# R650E.net
KiCad netlist of a schematic drawn in EAGLE
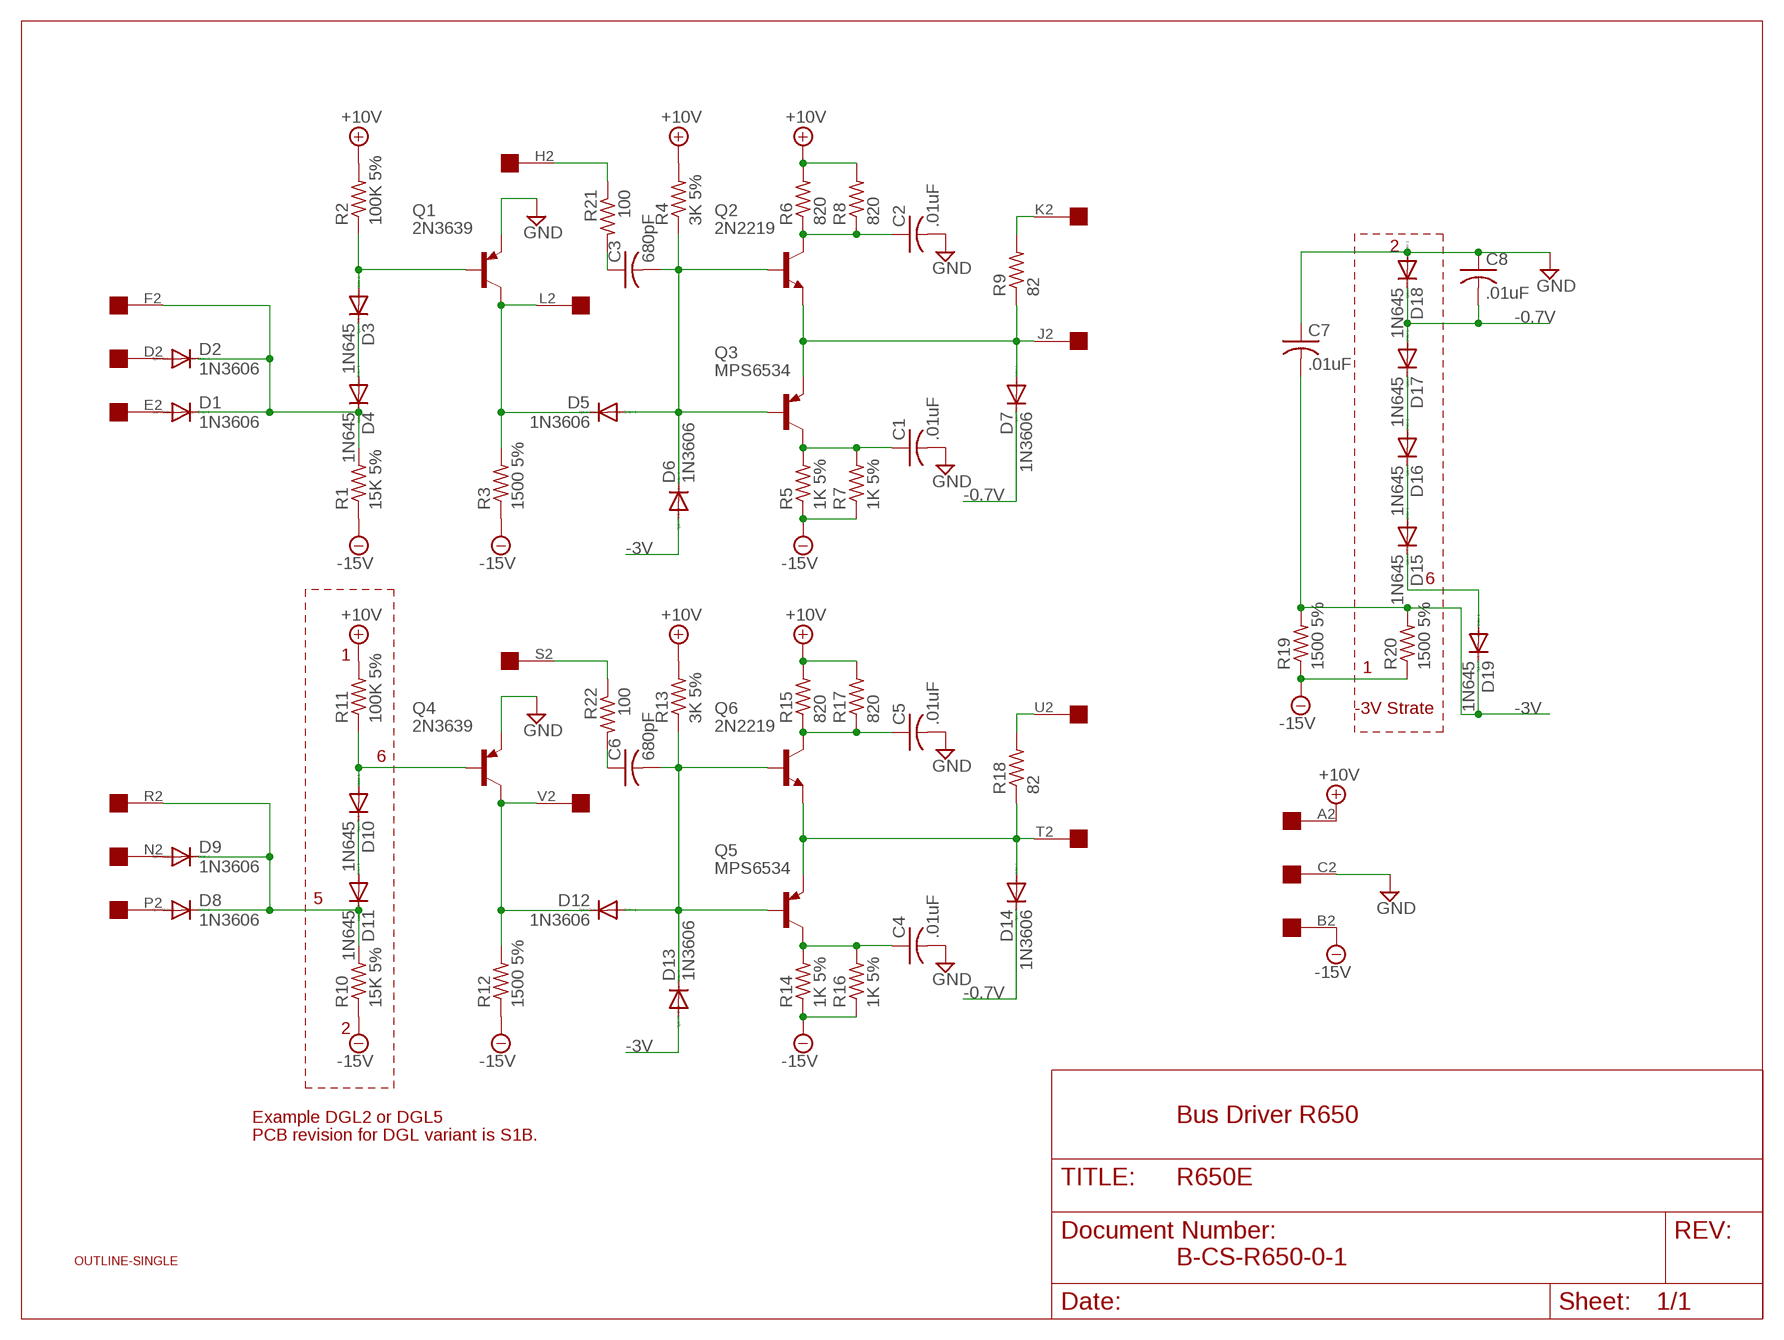
[diagram p0: schematic, sheet 1]

(export (version "E")
  (design (tool "Eeschema 10.0.6"))
  (components
    (comp (ref "C1")
      (value ".01uF")
      (footprint "eagle-import:C102-043X133")
      (libsource (lib "eagle-import") (part "C-US102-043X133"))
    )
    (comp (ref "C2")
      (value ".01uF")
      (footprint "eagle-import:C102-043X133")
      (libsource (lib "eagle-import") (part "C-US102-043X133"))
    )
    (comp (ref "C3")
      (value "680pF")
      (footprint "eagle-import:C102-043X133")
      (libsource (lib "eagle-import") (part "C-US102-043X133"))
    )
    (comp (ref "C4")
      (value ".01uF")
      (footprint "eagle-import:C102-043X133")
      (libsource (lib "eagle-import") (part "C-US102-043X133"))
    )
    (comp (ref "C5")
      (value ".01uF")
      (footprint "eagle-import:C102-043X133")
      (libsource (lib "eagle-import") (part "C-US102-043X133"))
    )
    (comp (ref "C6")
      (value "680pF")
      (footprint "eagle-import:C102-043X133")
      (libsource (lib "eagle-import") (part "C-US102-043X133"))
    )
    (comp (ref "C7")
      (value ".01uF")
      (footprint "eagle-import:C102-043X133")
      (libsource (lib "eagle-import") (part "C-US102-043X133"))
    )
    (comp (ref "C8")
      (value ".01uF")
      (footprint "eagle-import:C102-043X133")
      (libsource (lib "eagle-import") (part "C-US102-043X133"))
    )
    (comp (ref "D1")
      (value "1N3606")
      (footprint "eagle-import:DO35-10")
      (libsource (lib "eagle-import") (part "1N4148DO35-10"))
    )
    (comp (ref "D2")
      (value "1N3606")
      (footprint "eagle-import:DO35-10")
      (libsource (lib "eagle-import") (part "1N4148DO35-10"))
    )
    (comp (ref "D3")
      (value "1N645")
      (footprint "eagle-import:DO35-10")
      (libsource (lib "eagle-import") (part "1N4148DO35-10"))
    )
    (comp (ref "D4")
      (value "1N645")
      (footprint "eagle-import:DO35-10")
      (libsource (lib "eagle-import") (part "1N4148DO35-10"))
    )
    (comp (ref "D5")
      (value "1N3606")
      (footprint "eagle-import:DO35-10")
      (libsource (lib "eagle-import") (part "1N4148DO35-10"))
    )
    (comp (ref "D6")
      (value "1N3606")
      (footprint "eagle-import:DO35-10")
      (libsource (lib "eagle-import") (part "1N4148DO35-10"))
    )
    (comp (ref "D7")
      (value "1N3606")
      (footprint "eagle-import:DO35-10")
      (libsource (lib "eagle-import") (part "1N4148DO35-10"))
    )
    (comp (ref "D8")
      (value "1N3606")
      (footprint "eagle-import:DO35-10")
      (libsource (lib "eagle-import") (part "1N4148DO35-10"))
    )
    (comp (ref "D9")
      (value "1N3606")
      (footprint "eagle-import:DO35-10")
      (libsource (lib "eagle-import") (part "1N4148DO35-10"))
    )
    (comp (ref "D10")
      (value "1N645")
      (footprint "eagle-import:DO35-10")
      (libsource (lib "eagle-import") (part "1N4148DO35-10"))
    )
    (comp (ref "D11")
      (value "1N645")
      (footprint "eagle-import:DO35-10")
      (libsource (lib "eagle-import") (part "1N4148DO35-10"))
    )
    (comp (ref "D12")
      (value "1N3606")
      (footprint "eagle-import:DO35-10")
      (libsource (lib "eagle-import") (part "1N4148DO35-10"))
    )
    (comp (ref "D13")
      (value "1N3606")
      (footprint "eagle-import:DO35-10")
      (libsource (lib "eagle-import") (part "1N4148DO35-10"))
    )
    (comp (ref "D14")
      (value "1N3606")
      (footprint "eagle-import:DO35-10")
      (libsource (lib "eagle-import") (part "1N4148DO35-10"))
    )
    (comp (ref "D15")
      (value "1N645")
      (footprint "eagle-import:DO35-10")
      (libsource (lib "eagle-import") (part "1N4148DO35-10"))
    )
    (comp (ref "D16")
      (value "1N645")
      (footprint "eagle-import:DO35-10")
      (libsource (lib "eagle-import") (part "1N4148DO35-10"))
    )
    (comp (ref "D17")
      (value "1N645")
      (footprint "eagle-import:DO35-10")
      (libsource (lib "eagle-import") (part "1N4148DO35-10"))
    )
    (comp (ref "D18")
      (value "1N645")
      (footprint "eagle-import:DO35-10")
      (libsource (lib "eagle-import") (part "1N4148DO35-10"))
    )
    (comp (ref "D19")
      (value "1N645")
      (footprint "eagle-import:DO35-10")
      (libsource (lib "eagle-import") (part "1N4148DO35-10"))
    )
    (comp (ref "Q1")
      (value "2N3639")
      (footprint "eagle-import:TO39")
      (libsource (lib "eagle-import") (part "2N3637"))
    )
    (comp (ref "Q2")
      (value "2N2219")
      (footprint "eagle-import:TO5")
      (libsource (lib "eagle-import") (part "2N2219"))
    )
    (comp (ref "Q3")
      (value "MPS6534")
      (footprint "eagle-import:TO39")
      (libsource (lib "eagle-import") (part "2N3637"))
    )
    (comp (ref "Q4")
      (value "2N3639")
      (footprint "eagle-import:TO39")
      (libsource (lib "eagle-import") (part "2N3637"))
    )
    (comp (ref "Q5")
      (value "MPS6534")
      (footprint "eagle-import:TO39")
      (libsource (lib "eagle-import") (part "2N3637"))
    )
    (comp (ref "Q6")
      (value "2N2219")
      (footprint "eagle-import:TO5")
      (libsource (lib "eagle-import") (part "2N2219"))
    )
    (comp (ref "R1")
      (value "15K 5%")
      (footprint "eagle-import:0207_10")
      (libsource (lib "eagle-import") (part "R-US_0207/10"))
    )
    (comp (ref "R2")
      (value "100K 5%")
      (footprint "eagle-import:0207_10")
      (libsource (lib "eagle-import") (part "R-US_0207/10"))
    )
    (comp (ref "R3")
      (value "1500 5%")
      (footprint "eagle-import:0207_10")
      (libsource (lib "eagle-import") (part "R-US_0207/10"))
    )
    (comp (ref "R4")
      (value "3K 5%")
      (footprint "eagle-import:0207_10")
      (libsource (lib "eagle-import") (part "R-US_0207/10"))
    )
    (comp (ref "R5")
      (value "1K 5%")
      (footprint "eagle-import:0207_10")
      (libsource (lib "eagle-import") (part "R-US_0207/10"))
    )
    (comp (ref "R6")
      (value "820")
      (footprint "eagle-import:0207_10")
      (libsource (lib "eagle-import") (part "R-US_0207/10"))
    )
    (comp (ref "R7")
      (value "1K 5%")
      (footprint "eagle-import:0207_10")
      (libsource (lib "eagle-import") (part "R-US_0207/10"))
    )
    (comp (ref "R8")
      (value "820")
      (footprint "eagle-import:0207_10")
      (libsource (lib "eagle-import") (part "R-US_0207/10"))
    )
    (comp (ref "R9")
      (value "82")
      (footprint "eagle-import:0207_10")
      (libsource (lib "eagle-import") (part "R-US_0207/10"))
    )
    (comp (ref "R10")
      (value "15K 5%")
      (footprint "eagle-import:0207_10")
      (libsource (lib "eagle-import") (part "R-US_0207/10"))
    )
    (comp (ref "R11")
      (value "100K 5%")
      (footprint "eagle-import:0207_10")
      (libsource (lib "eagle-import") (part "R-US_0207/10"))
    )
    (comp (ref "R12")
      (value "1500 5%")
      (footprint "eagle-import:0207_10")
      (libsource (lib "eagle-import") (part "R-US_0207/10"))
    )
    (comp (ref "R13")
      (value "3K 5%")
      (footprint "eagle-import:0207_10")
      (libsource (lib "eagle-import") (part "R-US_0207/10"))
    )
    (comp (ref "R14")
      (value "1K 5%")
      (footprint "eagle-import:0207_10")
      (libsource (lib "eagle-import") (part "R-US_0207/10"))
    )
    (comp (ref "R15")
      (value "820")
      (footprint "eagle-import:0207_10")
      (libsource (lib "eagle-import") (part "R-US_0207/10"))
    )
    (comp (ref "R16")
      (value "1K 5%")
      (footprint "eagle-import:0207_10")
      (libsource (lib "eagle-import") (part "R-US_0207/10"))
    )
    (comp (ref "R17")
      (value "820")
      (footprint "eagle-import:0207_10")
      (libsource (lib "eagle-import") (part "R-US_0207/10"))
    )
    (comp (ref "R18")
      (value "82")
      (footprint "eagle-import:0207_10")
      (libsource (lib "eagle-import") (part "R-US_0207/10"))
    )
    (comp (ref "R19")
      (value "1500 5%")
      (footprint "eagle-import:0207_10")
      (libsource (lib "eagle-import") (part "R-US_0207/10"))
    )
    (comp (ref "R20")
      (value "1500 5%")
      (footprint "eagle-import:0207_10")
      (libsource (lib "eagle-import") (part "R-US_0207/10"))
    )
    (comp (ref "R21")
      (value "100")
      (footprint "eagle-import:0207_10")
      (libsource (lib "eagle-import") (part "R-US_0207/10"))
    )
    (comp (ref "R22")
      (value "100")
      (footprint "eagle-import:0207_10")
      (libsource (lib "eagle-import") (part "R-US_0207/10"))
    )
    (comp (ref "U$1")
      (value "OUTLINE-SINGLE")
      (footprint "eagle-import:SINGLE")
      (libsource (lib "eagle-import") (part "OUTLINE-SINGLE"))
    )
    (comp (ref "U$2")
      (value "EDGE-1")
      (footprint "eagle-import:EDGE-CON1")
      (libsource (lib "eagle-import") (part "EDGE-1"))
    )
  )
  (nets
    (net (code "1") (name "+10V") (class "Default")
      (node (ref "R11") (pin "2") (pinfunction "2_2") (pintype "passive"))
      (node (ref "R13") (pin "2") (pinfunction "2_2") (pintype "passive"))
      (node (ref "R15") (pin "2") (pinfunction "2_2") (pintype "passive"))
      (node (ref "R17") (pin "2") (pinfunction "2_2") (pintype "passive"))
      (node (ref "R2") (pin "2") (pinfunction "2_2") (pintype "passive"))
      (node (ref "R4") (pin "2") (pinfunction "2_2") (pintype "passive"))
      (node (ref "R6") (pin "2") (pinfunction "2_2") (pintype "passive"))
      (node (ref "R8") (pin "2") (pinfunction "2_2") (pintype "passive"))
      (node (ref "U$2") (pin "A2") (pinfunction "1_A2") (pintype "bidirectional"))
    )
    (net (code "2") (name "-15V") (class "Default")
      (node (ref "R1") (pin "1") (pinfunction "1_1") (pintype "passive"))
      (node (ref "R10") (pin "1") (pinfunction "1_1") (pintype "passive"))
      (node (ref "R12") (pin "1") (pinfunction "1_1") (pintype "passive"))
      (node (ref "R14") (pin "1") (pinfunction "1_1") (pintype "passive"))
      (node (ref "R16") (pin "1") (pinfunction "1_1") (pintype "passive"))
      (node (ref "R19") (pin "1") (pinfunction "1_1") (pintype "passive"))
      (node (ref "R20") (pin "1") (pinfunction "1_1") (pintype "passive"))
      (node (ref "R3") (pin "1") (pinfunction "1_1") (pintype "passive"))
      (node (ref "R5") (pin "1") (pinfunction "1_1") (pintype "passive"))
      (node (ref "R7") (pin "1") (pinfunction "1_1") (pintype "passive"))
      (node (ref "U$2") (pin "B2") (pinfunction "1_B2") (pintype "bidirectional"))
    )
    (net (code "3") (name "/-0.7V") (class "Default")
      (node (ref "C8") (pin "2") (pinfunction "2_2") (pintype "passive"))
      (node (ref "D14") (pin "C") (pinfunction "C_C") (pintype "passive"))
      (node (ref "D17") (pin "A") (pinfunction "A_A") (pintype "passive"))
      (node (ref "D18") (pin "C") (pinfunction "C_C") (pintype "passive"))
      (node (ref "D7") (pin "C") (pinfunction "C_C") (pintype "passive"))
    )
    (net (code "4") (name "/-3V") (class "Default")
      (node (ref "C7") (pin "2") (pinfunction "2_2") (pintype "passive"))
      (node (ref "D13") (pin "A") (pinfunction "A_A") (pintype "passive"))
      (node (ref "D19") (pin "C") (pinfunction "C_C") (pintype "passive"))
      (node (ref "D6") (pin "A") (pinfunction "A_A") (pintype "passive"))
      (node (ref "R19") (pin "2") (pinfunction "2_2") (pintype "passive"))
      (node (ref "R20") (pin "2") (pinfunction "2_2") (pintype "passive"))
    )
    (net (code "5") (name "GND") (class "Default")
      (node (ref "C1") (pin "2") (pinfunction "2_2") (pintype "passive"))
      (node (ref "C2") (pin "2") (pinfunction "2_2") (pintype "passive"))
      (node (ref "C4") (pin "2") (pinfunction "2_2") (pintype "passive"))
      (node (ref "C5") (pin "2") (pinfunction "2_2") (pintype "passive"))
      (node (ref "C7") (pin "1") (pinfunction "1_1") (pintype "passive"))
      (node (ref "C8") (pin "1") (pinfunction "1_1") (pintype "passive"))
      (node (ref "D18") (pin "A") (pinfunction "A_A") (pintype "passive"))
      (node (ref "Q1") (pin "1") (pinfunction "E_1") (pintype "passive"))
      (node (ref "Q4") (pin "1") (pinfunction "E_1") (pintype "passive"))
      (node (ref "U$2") (pin "C2") (pinfunction "1_C2") (pintype "bidirectional"))
    )
    (net (code "6") (name "Net-(C3-Pad1)") (class "Default")
      (node (ref "C3") (pin "1") (pinfunction "1_1") (pintype "passive"))
      (node (ref "R21") (pin "2") (pinfunction "2_2") (pintype "passive"))
    )
    (net (code "7") (name "Net-(C6-Pad1)") (class "Default")
      (node (ref "C6") (pin "1") (pinfunction "1_1") (pintype "passive"))
      (node (ref "R22") (pin "2") (pinfunction "2_2") (pintype "passive"))
    )
    (net (code "8") (name "Net-(D3-PadC)") (class "Default")
      (node (ref "D3") (pin "C") (pinfunction "C_C") (pintype "passive"))
      (node (ref "D4") (pin "A") (pinfunction "A_A") (pintype "passive"))
    )
    (net (code "9") (name "Net-(D10-PadC)") (class "Default")
      (node (ref "D10") (pin "C") (pinfunction "C_C") (pintype "passive"))
      (node (ref "D11") (pin "A") (pinfunction "A_A") (pintype "passive"))
    )
    (net (code "10") (name "Net-(D15-PadA)") (class "Default")
      (node (ref "D15") (pin "A") (pinfunction "A_A") (pintype "passive"))
      (node (ref "D16") (pin "C") (pinfunction "C_C") (pintype "passive"))
    )
    (net (code "11") (name "Net-(D15-PadC)") (class "Default")
      (node (ref "D15") (pin "C") (pinfunction "C_C") (pintype "passive"))
      (node (ref "D19") (pin "A") (pinfunction "A_A") (pintype "passive"))
    )
    (net (code "12") (name "Net-(D16-PadA)") (class "Default")
      (node (ref "D16") (pin "A") (pinfunction "A_A") (pintype "passive"))
      (node (ref "D17") (pin "C") (pinfunction "C_C") (pintype "passive"))
    )
    (net (code "13") (name "Net-(Q1-B)") (class "Default")
      (node (ref "D3") (pin "A") (pinfunction "A_A") (pintype "passive"))
      (node (ref "Q1") (pin "2") (pinfunction "B_2") (pintype "passive"))
      (node (ref "R2") (pin "1") (pinfunction "1_1") (pintype "passive"))
    )
    (net (code "14") (name "Net-(Q1-C)") (class "Default")
      (node (ref "D5") (pin "C") (pinfunction "C_C") (pintype "passive"))
      (node (ref "Q1") (pin "3") (pinfunction "C_3") (pintype "passive"))
      (node (ref "R3") (pin "2") (pinfunction "2_2") (pintype "passive"))
      (node (ref "U$2") (pin "L2") (pinfunction "1_L2") (pintype "bidirectional"))
    )
    (net (code "15") (name "Net-(Q2-B)") (class "Default")
      (node (ref "C3") (pin "2") (pinfunction "2_2") (pintype "passive"))
      (node (ref "D5") (pin "A") (pinfunction "A_A") (pintype "passive"))
      (node (ref "D6") (pin "C") (pinfunction "C_C") (pintype "passive"))
      (node (ref "Q2") (pin "2") (pinfunction "B_2") (pintype "passive"))
      (node (ref "Q3") (pin "2") (pinfunction "B_2") (pintype "passive"))
      (node (ref "R4") (pin "1") (pinfunction "1_1") (pintype "passive"))
    )
    (net (code "16") (name "Net-(Q2-C)") (class "Default")
      (node (ref "C2") (pin "1") (pinfunction "1_1") (pintype "passive"))
      (node (ref "Q2") (pin "3") (pinfunction "C_3") (pintype "passive"))
      (node (ref "R6") (pin "1") (pinfunction "1_1") (pintype "passive"))
      (node (ref "R8") (pin "1") (pinfunction "1_1") (pintype "passive"))
    )
    (net (code "17") (name "Net-(Q2-E)") (class "Default")
      (node (ref "D7") (pin "A") (pinfunction "A_A") (pintype "passive"))
      (node (ref "Q2") (pin "1") (pinfunction "E_1") (pintype "passive"))
      (node (ref "Q3") (pin "1") (pinfunction "E_1") (pintype "passive"))
      (node (ref "R9") (pin "1") (pinfunction "1_1") (pintype "passive"))
      (node (ref "U$2") (pin "J2") (pinfunction "1_J2") (pintype "bidirectional"))
    )
    (net (code "18") (name "Net-(Q3-C)") (class "Default")
      (node (ref "C1") (pin "1") (pinfunction "1_1") (pintype "passive"))
      (node (ref "Q3") (pin "3") (pinfunction "C_3") (pintype "passive"))
      (node (ref "R5") (pin "2") (pinfunction "2_2") (pintype "passive"))
      (node (ref "R7") (pin "2") (pinfunction "2_2") (pintype "passive"))
    )
    (net (code "19") (name "Net-(Q4-B)") (class "Default")
      (node (ref "D10") (pin "A") (pinfunction "A_A") (pintype "passive"))
      (node (ref "Q4") (pin "2") (pinfunction "B_2") (pintype "passive"))
      (node (ref "R11") (pin "1") (pinfunction "1_1") (pintype "passive"))
    )
    (net (code "20") (name "Net-(Q4-C)") (class "Default")
      (node (ref "D12") (pin "C") (pinfunction "C_C") (pintype "passive"))
      (node (ref "Q4") (pin "3") (pinfunction "C_3") (pintype "passive"))
      (node (ref "R12") (pin "2") (pinfunction "2_2") (pintype "passive"))
      (node (ref "U$2") (pin "V2") (pinfunction "1_V2") (pintype "bidirectional"))
    )
    (net (code "21") (name "Net-(Q5-B)") (class "Default")
      (node (ref "C6") (pin "2") (pinfunction "2_2") (pintype "passive"))
      (node (ref "D12") (pin "A") (pinfunction "A_A") (pintype "passive"))
      (node (ref "D13") (pin "C") (pinfunction "C_C") (pintype "passive"))
      (node (ref "Q5") (pin "2") (pinfunction "B_2") (pintype "passive"))
      (node (ref "Q6") (pin "2") (pinfunction "B_2") (pintype "passive"))
      (node (ref "R13") (pin "1") (pinfunction "1_1") (pintype "passive"))
    )
    (net (code "22") (name "Net-(Q5-C)") (class "Default")
      (node (ref "C4") (pin "1") (pinfunction "1_1") (pintype "passive"))
      (node (ref "Q5") (pin "3") (pinfunction "C_3") (pintype "passive"))
      (node (ref "R14") (pin "2") (pinfunction "2_2") (pintype "passive"))
      (node (ref "R16") (pin "2") (pinfunction "2_2") (pintype "passive"))
    )
    (net (code "23") (name "Net-(Q5-E)") (class "Default")
      (node (ref "D14") (pin "A") (pinfunction "A_A") (pintype "passive"))
      (node (ref "Q5") (pin "1") (pinfunction "E_1") (pintype "passive"))
      (node (ref "Q6") (pin "1") (pinfunction "E_1") (pintype "passive"))
      (node (ref "R18") (pin "1") (pinfunction "1_1") (pintype "passive"))
      (node (ref "U$2") (pin "T2") (pinfunction "1_T2") (pintype "bidirectional"))
    )
    (net (code "24") (name "Net-(Q6-C)") (class "Default")
      (node (ref "C5") (pin "1") (pinfunction "1_1") (pintype "passive"))
      (node (ref "Q6") (pin "3") (pinfunction "C_3") (pintype "passive"))
      (node (ref "R15") (pin "1") (pinfunction "1_1") (pintype "passive"))
      (node (ref "R17") (pin "1") (pinfunction "1_1") (pintype "passive"))
    )
    (net (code "25") (name "Net-(U$2D-1)") (class "Default")
      (node (ref "D2") (pin "A") (pinfunction "A_A") (pintype "passive"))
      (node (ref "U$2") (pin "D2") (pinfunction "1_D2") (pintype "bidirectional"))
    )
    (net (code "26") (name "Net-(U$2E-1)") (class "Default")
      (node (ref "D1") (pin "A") (pinfunction "A_A") (pintype "passive"))
      (node (ref "U$2") (pin "E2") (pinfunction "1_E2") (pintype "bidirectional"))
    )
    (net (code "27") (name "Net-(U$2F-1)") (class "Default")
      (node (ref "D1") (pin "C") (pinfunction "C_C") (pintype "passive"))
      (node (ref "D2") (pin "C") (pinfunction "C_C") (pintype "passive"))
      (node (ref "D4") (pin "C") (pinfunction "C_C") (pintype "passive"))
      (node (ref "R1") (pin "2") (pinfunction "2_2") (pintype "passive"))
      (node (ref "U$2") (pin "F2") (pinfunction "1_F2") (pintype "bidirectional"))
    )
    (net (code "28") (name "Net-(U$2G-1)") (class "Default")
      (node (ref "R21") (pin "1") (pinfunction "1_1") (pintype "passive"))
      (node (ref "U$2") (pin "H2") (pinfunction "1_H2") (pintype "bidirectional"))
    )
    (net (code "29") (name "Net-(U$2I-1)") (class "Default")
      (node (ref "R9") (pin "2") (pinfunction "2_2") (pintype "passive"))
      (node (ref "U$2") (pin "K2") (pinfunction "1_K2") (pintype "bidirectional"))
    )
    (net (code "30") (name "Net-(U$2L-1)") (class "Default")
      (node (ref "D9") (pin "A") (pinfunction "A_A") (pintype "passive"))
      (node (ref "U$2") (pin "N2") (pinfunction "1_N2") (pintype "bidirectional"))
    )
    (net (code "31") (name "Net-(U$2M-1)") (class "Default")
      (node (ref "D8") (pin "A") (pinfunction "A_A") (pintype "passive"))
      (node (ref "U$2") (pin "P2") (pinfunction "1_P2") (pintype "bidirectional"))
    )
    (net (code "32") (name "Net-(U$2N-1)") (class "Default")
      (node (ref "D11") (pin "C") (pinfunction "C_C") (pintype "passive"))
      (node (ref "D8") (pin "C") (pinfunction "C_C") (pintype "passive"))
      (node (ref "D9") (pin "C") (pinfunction "C_C") (pintype "passive"))
      (node (ref "R10") (pin "2") (pinfunction "2_2") (pintype "passive"))
      (node (ref "U$2") (pin "R2") (pinfunction "1_R2") (pintype "bidirectional"))
    )
    (net (code "33") (name "Net-(U$2O-1)") (class "Default")
      (node (ref "R22") (pin "1") (pinfunction "1_1") (pintype "passive"))
      (node (ref "U$2") (pin "S2") (pinfunction "1_S2") (pintype "bidirectional"))
    )
    (net (code "34") (name "Net-(U$2Q-1)") (class "Default")
      (node (ref "R18") (pin "2") (pinfunction "2_2") (pintype "passive"))
      (node (ref "U$2") (pin "U2") (pinfunction "1_U2") (pintype "bidirectional"))
    )
  )
)
